# SCH_SCore-SR1_2025-01-31.net
KiCad netlist of a schematic drawn in EasyEDA
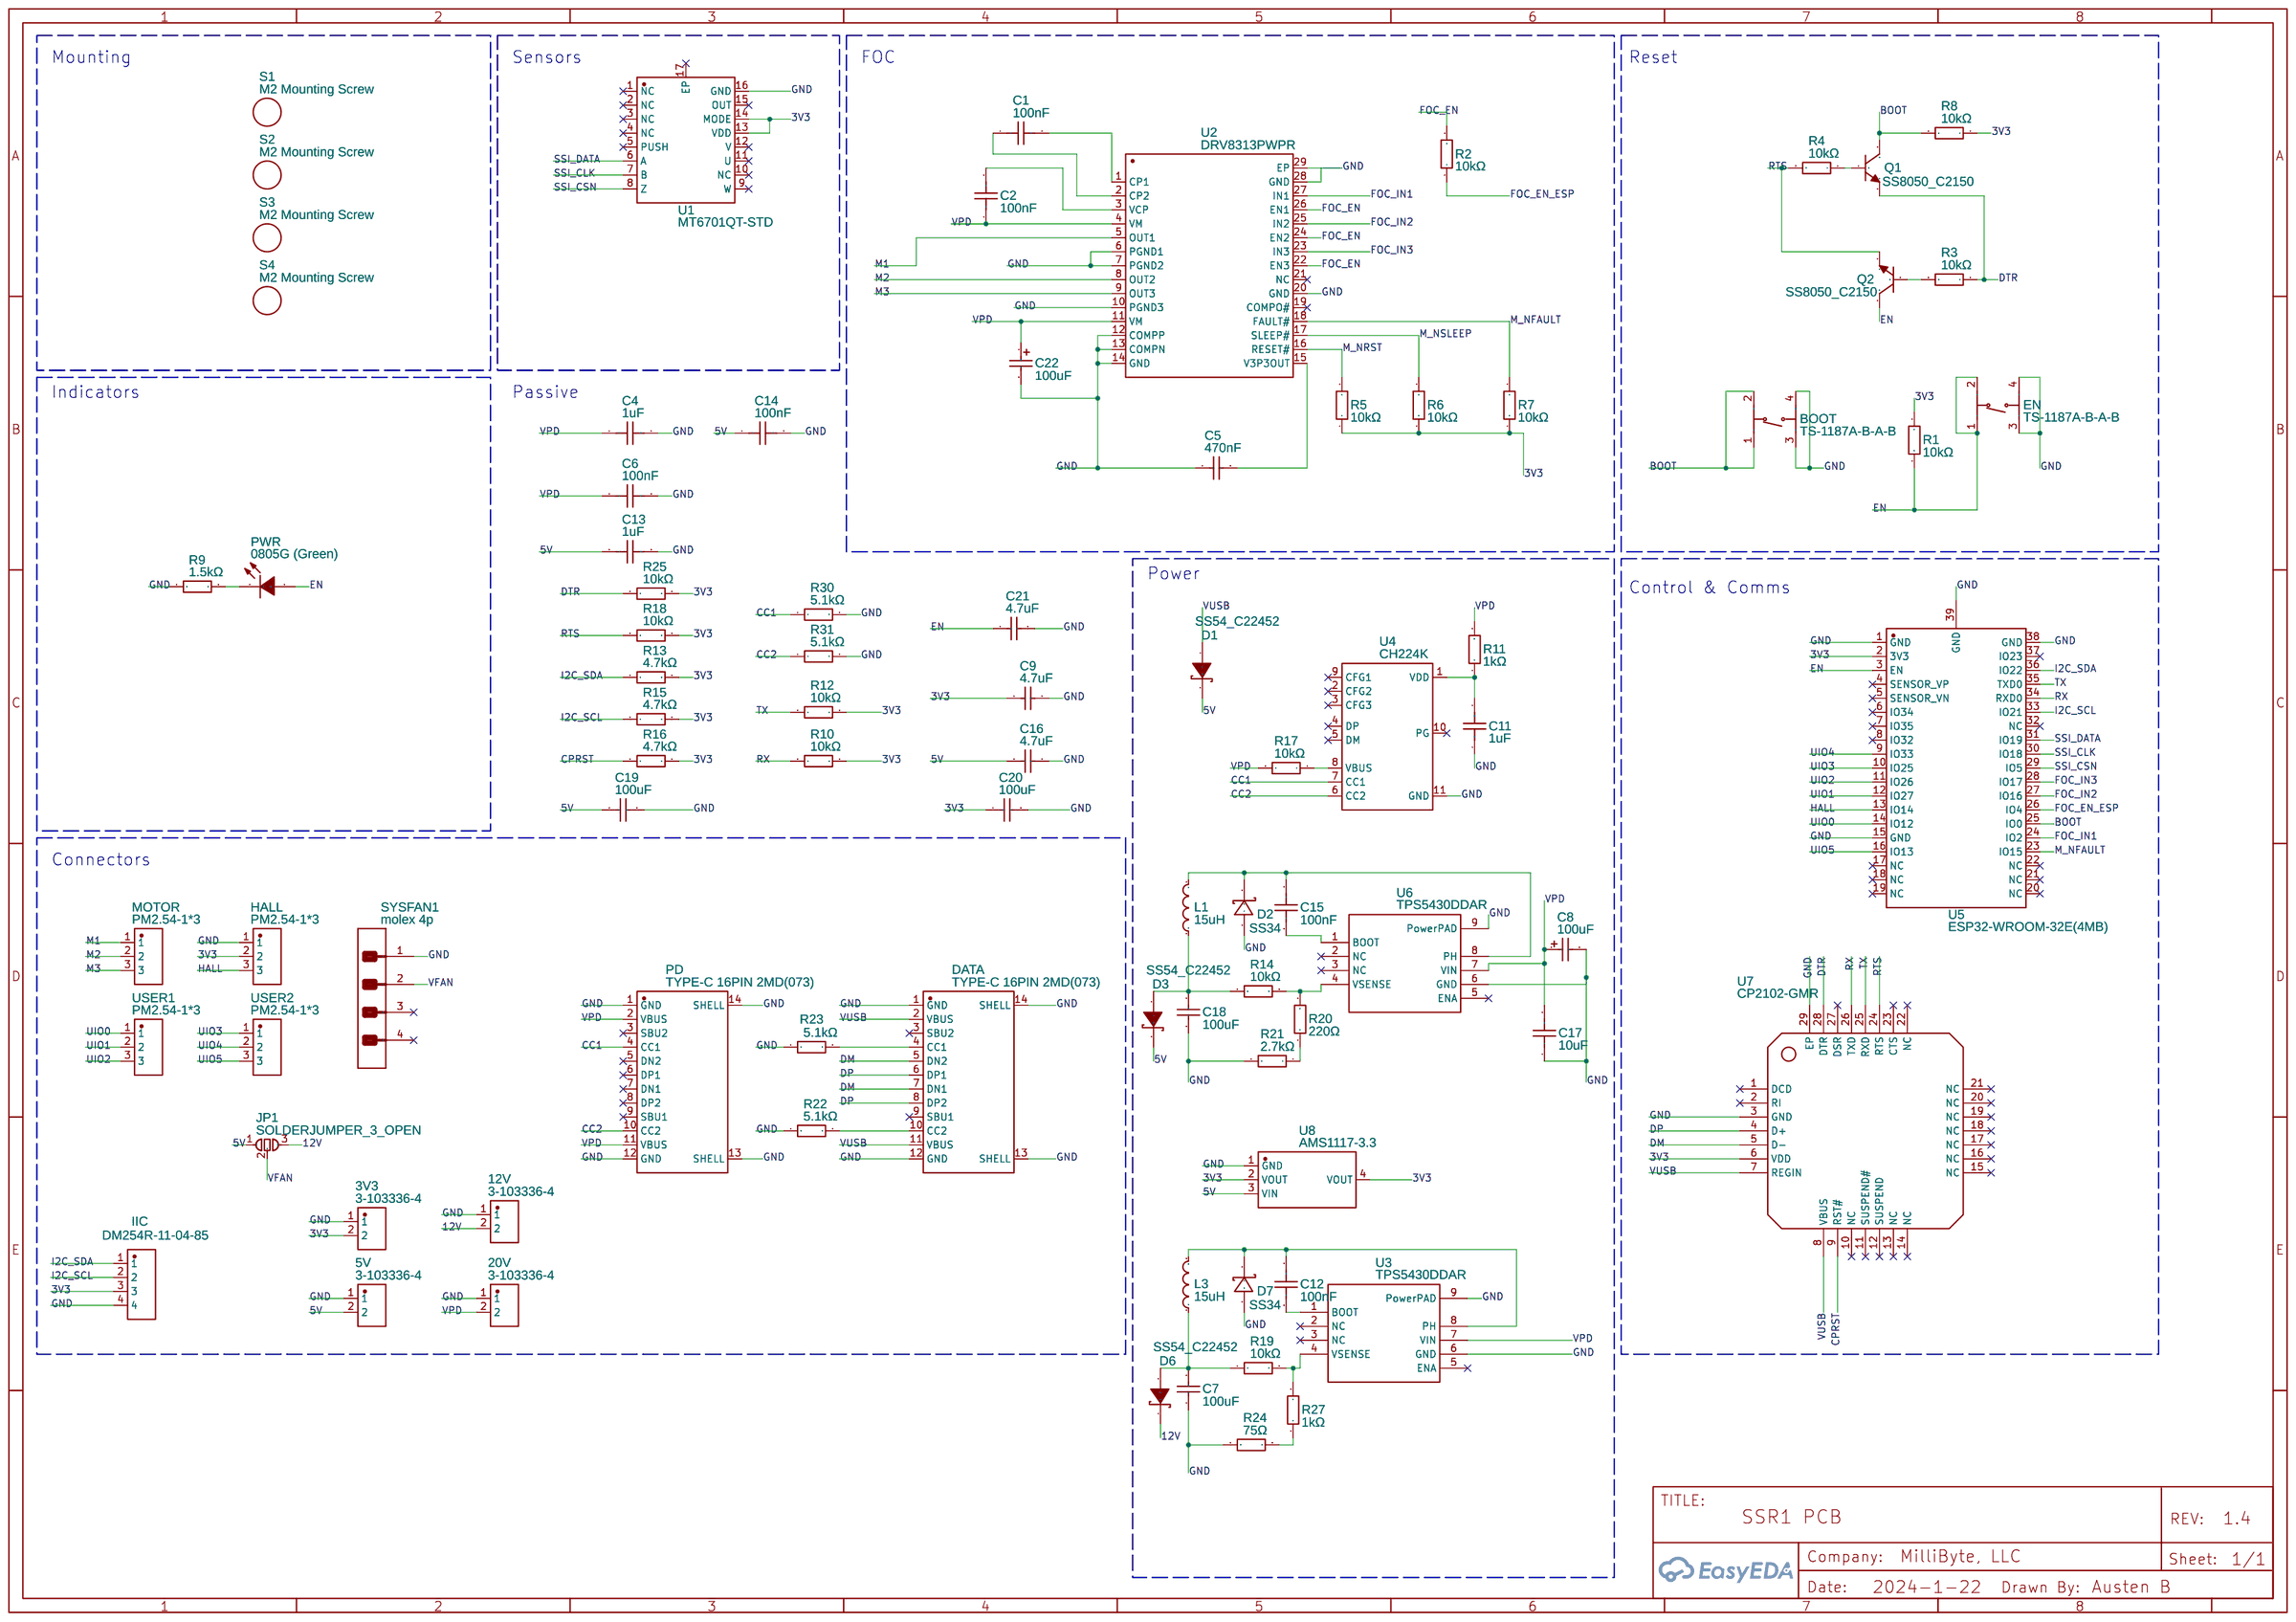
[diagram p0: schematic sheet]

(export (version "E")
  (design (tool "Eeschema 10.0.6"))
  (components
    (comp (ref "3V3")
      (value "3-103336-4")
      (fields (field (name "Manufacturer") "TE Connectivity(泰科电子)"))
      (libsource (lib "") (part "3-103336-4"))
    )
    (comp (ref "5V")
      (value "3-103336-4")
      (fields (field (name "Manufacturer") "TE Connectivity(泰科电子)"))
      (libsource (lib "") (part "3-103336-4_2"))
    )
    (comp (ref "12V")
      (value "3-103336-4")
      (fields (field (name "Manufacturer") "TE Connectivity(泰科电子)"))
      (libsource (lib "") (part "3-103336-4_1"))
    )
    (comp (ref "20V")
      (value "3-103336-4")
      (fields (field (name "Manufacturer") "TE Connectivity(泰科电子)"))
      (libsource (lib "") (part "3-103336-4_3"))
    )
    (comp (ref "BOOT")
      (value "TS-1187A-B-A-B")
      (fields (field (name "Manufacturer") "XKB Connectivity(中国星坤)"))
      (libsource (lib "") (part "TS-1187A-B-A-B_1"))
    )
    (comp (ref "C1")
      (value "100nF")
      (fields
        (field (name "Manufacturer Part") "CC0603KRX7R9BB104")
        (field (name "Manufacturer") "YAGEO(国巨)")
      )
      (libsource (lib "") (part "CC0603KRX7R9BB104"))
    )
    (comp (ref "C2")
      (value "100nF")
      (fields
        (field (name "Manufacturer Part") "CC0603KRX7R9BB104")
        (field (name "Manufacturer") "YAGEO(国巨)")
      )
      (libsource (lib "") (part "CC0603KRX7R9BB104_2"))
    )
    (comp (ref "C4")
      (value "1uF")
      (fields
        (field (name "Manufacturer Part") "CL10A105KB8NNNC")
        (field (name "Manufacturer") "SAMSUNG(三星)")
      )
      (libsource (lib "") (part "CL10A105KB8NNNC_1"))
    )
    (comp (ref "C5")
      (value "470nF")
      (fields
        (field (name "Manufacturer Part") "CL21B474KBFNNNE")
        (field (name "Manufacturer") "SAMSUNG(三星)")
      )
      (libsource (lib "") (part "CL21B474KBFNNNE"))
    )
    (comp (ref "C6")
      (value "100nF")
      (fields
        (field (name "Manufacturer Part") "CC0603KRX7R9BB104")
        (field (name "Manufacturer") "YAGEO(国巨)")
      )
      (libsource (lib "") (part "CC0603KRX7R9BB104"))
    )
    (comp (ref "C7")
      (value "100uF")
      (fields
        (field (name "Manufacturer Part") "CL31A107MQHNNNE")
        (field (name "Manufacturer") "SAMSUNG(三星)")
      )
      (libsource (lib "") (part "CL31A107MQHNNNE_1"))
    )
    (comp (ref "C8")
      (value "100uF")
      (fields (field (name "Manufacturer Part") "20TQC100MYF") (field (name "Manufacturer") "PANASONIC(松下)"))
      (libsource (lib "") (part "20TQC100MYF_1"))
    )
    (comp (ref "C9")
      (value "4.7uF")
      (fields
        (field (name "Manufacturer Part") "CL05A475MP5NRNC")
        (field (name "Manufacturer") "SAMSUNG(三星)")
      )
      (libsource (lib "") (part "CL05A475MP5NRNC"))
    )
    (comp (ref "C11")
      (value "1uF")
      (fields
        (field (name "Manufacturer Part") "CL10A105KB8NNNC")
        (field (name "Manufacturer") "SAMSUNG(三星)")
      )
      (libsource (lib "") (part "CL10A105KB8NNNC"))
    )
    (comp (ref "C12")
      (value "100nF")
      (fields
        (field (name "Manufacturer Part") "CC0603KRX7R9BB104")
        (field (name "Manufacturer") "YAGEO(国巨)")
      )
      (libsource (lib "") (part "CC0603KRX7R9BB104_1"))
    )
    (comp (ref "C13")
      (value "1uF")
      (fields
        (field (name "Manufacturer Part") "CL10A105KB8NNNC")
        (field (name "Manufacturer") "SAMSUNG(三星)")
      )
      (libsource (lib "") (part "CL10A105KB8NNNC_1"))
    )
    (comp (ref "C14")
      (value "100nF")
      (fields
        (field (name "Manufacturer Part") "CC0603KRX7R9BB104")
        (field (name "Manufacturer") "YAGEO(国巨)")
      )
      (libsource (lib "") (part "CC0603KRX7R9BB104"))
    )
    (comp (ref "C15")
      (value "100nF")
      (fields
        (field (name "Manufacturer Part") "CC0603KRX7R9BB104")
        (field (name "Manufacturer") "YAGEO(国巨)")
      )
      (libsource (lib "") (part "CC0603KRX7R9BB104_1"))
    )
    (comp (ref "C16")
      (value "4.7uF")
      (fields
        (field (name "Manufacturer Part") "CL05A475MP5NRNC")
        (field (name "Manufacturer") "SAMSUNG(三星)")
      )
      (libsource (lib "") (part "CL05A475MP5NRNC"))
    )
    (comp (ref "C17")
      (value "10uF")
      (fields
        (field (name "Manufacturer Part") "CL21A106KAYNNNE")
        (field (name "Manufacturer") "SAMSUNG(三星)")
      )
      (libsource (lib "") (part "CL21A106KAYNNNE"))
    )
    (comp (ref "C18")
      (value "100uF")
      (fields
        (field (name "Manufacturer Part") "CL31A107MQHNNNE")
        (field (name "Manufacturer") "SAMSUNG(三星)")
      )
      (libsource (lib "") (part "CL31A107MQHNNNE_1"))
    )
    (comp (ref "C19")
      (value "100uF")
      (fields
        (field (name "Manufacturer Part") "CL31A107MQHNNNE")
        (field (name "Manufacturer") "SAMSUNG(三星)")
      )
      (libsource (lib "") (part "CL31A107MQHNNNE"))
    )
    (comp (ref "C20")
      (value "100uF")
      (fields
        (field (name "Manufacturer Part") "CL31A107MQHNNNE")
        (field (name "Manufacturer") "SAMSUNG(三星)")
      )
      (libsource (lib "") (part "CL31A107MQHNNNE"))
    )
    (comp (ref "C21")
      (value "4.7uF")
      (fields
        (field (name "Manufacturer Part") "CL05A475MP5NRNC")
        (field (name "Manufacturer") "SAMSUNG(三星)")
      )
      (libsource (lib "") (part "CL05A475MP5NRNC"))
    )
    (comp (ref "C22")
      (value "100uF")
      (fields (field (name "Manufacturer Part") "20TQC100MYF") (field (name "Manufacturer") "PANASONIC(松下)"))
      (libsource (lib "") (part "20TQC100MYF"))
    )
    (comp (ref "D1")
      (value "SS54_C22452")
      (fields (field (name "Manufacturer Part") "SS54") (field (name "Manufacturer") "MDD"))
      (libsource (lib "") (part "SS54_C22452"))
    )
    (comp (ref "D2")
      (value "SS34")
      (fields (field (name "Manufacturer") "MDD(辰达半导体)"))
      (libsource (lib "") (part "SS34_C8678"))
    )
    (comp (ref "D3")
      (value "SS54_C22452")
      (fields (field (name "Manufacturer Part") "SS54") (field (name "Manufacturer") "MDD"))
      (libsource (lib "") (part "SS54_C22452"))
    )
    (comp (ref "D6")
      (value "SS54_C22452")
      (fields (field (name "Manufacturer Part") "SS54") (field (name "Manufacturer") "MDD"))
      (libsource (lib "") (part "SS54_C22452"))
    )
    (comp (ref "D7")
      (value "SS34")
      (fields (field (name "Manufacturer") "MDD(辰达半导体)"))
      (libsource (lib "") (part "SS34_C8678"))
    )
    (comp (ref "DATA")
      (value "TYPE-C 16PIN 2MD(073)")
      (fields (field (name "Manufacturer") "SHOU HAN(首韩)"))
      (libsource (lib "") (part "TYPE-C 16PIN 2MD(073)_1"))
    )
    (comp (ref "EN")
      (value "TS-1187A-B-A-B")
      (fields (field (name "Manufacturer") "XKB Connectivity(中国星坤)"))
      (libsource (lib "") (part "TS-1187A-B-A-B"))
    )
    (comp (ref "HALL")
      (value "PM2.54-1*3")
      (fields (field (name "Manufacturer") "ZHOURI(洲日)"))
      (libsource (lib "") (part "PM2.54-1*3_2"))
    )
    (comp (ref "IIC")
      (value "DM254R-11-04-85")
      (fields (field (name "Manufacturer") "DEALON(德艺隆)"))
      (libsource (lib "") (part "DM254R-11-04-85"))
    )
    (comp (ref "JP1") (value "SOLDERJUMPER_3_OPEN") (libsource (lib "") (part "SOLDERJUMPER_3_OPEN")))
    (comp (ref "L1")
      (value "15uH")
      (fields
        (field (name "Manufacturer Part") "MWSA0603S-150MT")
        (field (name "Manufacturer") "Sunlord(顺络)")
      )
      (libsource (lib "") (part "MWSA0603S-150MT_1"))
    )
    (comp (ref "L3")
      (value "15uH")
      (fields
        (field (name "Manufacturer Part") "MWSA0603S-150MT")
        (field (name "Manufacturer") "Sunlord(顺络)")
      )
      (libsource (lib "") (part "MWSA0603S-150MT"))
    )
    (comp (ref "MOTOR")
      (value "PM2.54-1*3")
      (fields (field (name "Manufacturer") "ZHOURI(洲日)"))
      (libsource (lib "") (part "PM2.54-1*3_1"))
    )
    (comp (ref "PD")
      (value "TYPE-C 16PIN 2MD(073)")
      (fields (field (name "Manufacturer") "SHOU HAN(首韩)"))
      (libsource (lib "") (part "TYPE-C 16PIN 2MD(073)"))
    )
    (comp (ref "PWR")
      (value "0805G (Green)")
      (fields (field (name "Manufacturer Part") "KT-0805G") (field (name "Manufacturer") "KENTO"))
      (libsource (lib "") (part "0805G (Green)"))
    )
    (comp (ref "Q1")
      (value "SS8050_C2150")
      (fields (field (name "Manufacturer Part") "SS8050") (field (name "Manufacturer") "CJ(江苏长电/长晶)"))
      (libsource (lib "") (part "SS8050_C2150"))
    )
    (comp (ref "Q2")
      (value "SS8050_C2150")
      (fields (field (name "Manufacturer Part") "SS8050") (field (name "Manufacturer") "CJ(江苏长电/长晶)"))
      (libsource (lib "") (part "SS8050_C2150_1"))
    )
    (comp (ref "R1")
      (value "10kΩ")
      (fields
        (field (name "Manufacturer Part") "0402WGF1002TCE")
        (field (name "Manufacturer") "UNI-ROYAL(厚声)")
      )
      (libsource (lib "") (part "0402WGF1002TCE_2"))
    )
    (comp (ref "R2")
      (value "10kΩ")
      (fields
        (field (name "Manufacturer Part") "0603WAF1002T5E")
        (field (name "Manufacturer") "UNI-ROYAL(厚声)")
      )
      (libsource (lib "") (part "0603WAF1002T5E"))
    )
    (comp (ref "R3")
      (value "10kΩ")
      (fields
        (field (name "Manufacturer Part") "0402WGF1002TCE")
        (field (name "Manufacturer") "UNI-ROYAL(厚声)")
      )
      (libsource (lib "") (part "0402WGF1002TCE"))
    )
    (comp (ref "R4")
      (value "10kΩ")
      (fields
        (field (name "Manufacturer Part") "0402WGF1002TCE")
        (field (name "Manufacturer") "UNI-ROYAL(厚声)")
      )
      (libsource (lib "") (part "0402WGF1002TCE"))
    )
    (comp (ref "R5")
      (value "10kΩ")
      (fields
        (field (name "Manufacturer Part") "0402WGF1002TCE")
        (field (name "Manufacturer") "UNI-ROYAL(厚声)")
      )
      (libsource (lib "") (part "0402WGF1002TCE_2"))
    )
    (comp (ref "R6")
      (value "10kΩ")
      (fields
        (field (name "Manufacturer Part") "0402WGF1002TCE")
        (field (name "Manufacturer") "UNI-ROYAL(厚声)")
      )
      (libsource (lib "") (part "0402WGF1002TCE_2"))
    )
    (comp (ref "R7")
      (value "10kΩ")
      (fields
        (field (name "Manufacturer Part") "0402WGF1002TCE")
        (field (name "Manufacturer") "UNI-ROYAL(厚声)")
      )
      (libsource (lib "") (part "0402WGF1002TCE_2"))
    )
    (comp (ref "R8")
      (value "10kΩ")
      (fields
        (field (name "Manufacturer Part") "0402WGF1002TCE")
        (field (name "Manufacturer") "UNI-ROYAL(厚声)")
      )
      (libsource (lib "") (part "0402WGF1002TCE"))
    )
    (comp (ref "R9")
      (value "1.5kΩ")
      (fields
        (field (name "Manufacturer Part") "0603WAF1501T5E")
        (field (name "Manufacturer") "UNI-ROYAL(厚声)")
      )
      (libsource (lib "") (part "0603WAF1501T5E"))
    )
    (comp (ref "R10")
      (value "10kΩ")
      (fields
        (field (name "Manufacturer Part") "0402WGF1002TCE")
        (field (name "Manufacturer") "UNI-ROYAL(厚声)")
      )
      (libsource (lib "") (part "0402WGF1002TCE_1"))
    )
    (comp (ref "R11")
      (value "1kΩ")
      (fields
        (field (name "Manufacturer Part") "0402WGF1001TCE")
        (field (name "Manufacturer") "UNI-ROYAL(厚声)")
      )
      (libsource (lib "") (part "0402WGF1001TCE"))
    )
    (comp (ref "R12")
      (value "10kΩ")
      (fields
        (field (name "Manufacturer Part") "0402WGF1002TCE")
        (field (name "Manufacturer") "UNI-ROYAL(厚声)")
      )
      (libsource (lib "") (part "0402WGF1002TCE_1"))
    )
    (comp (ref "R13")
      (value "4.7kΩ")
      (fields
        (field (name "Manufacturer Part") "0402WGF4701TCE")
        (field (name "Manufacturer") "UNI-ROYAL(厚声)")
      )
      (libsource (lib "") (part "0402WGF4701TCE"))
    )
    (comp (ref "R14")
      (value "10kΩ")
      (fields
        (field (name "Manufacturer Part") "0402WGF1002TCE")
        (field (name "Manufacturer") "UNI-ROYAL(厚声)")
      )
      (libsource (lib "") (part "0402WGF1002TCE_1"))
    )
    (comp (ref "R15")
      (value "4.7kΩ")
      (fields
        (field (name "Manufacturer Part") "0402WGF4701TCE")
        (field (name "Manufacturer") "UNI-ROYAL(厚声)")
      )
      (libsource (lib "") (part "0402WGF4701TCE"))
    )
    (comp (ref "R16")
      (value "4.7kΩ")
      (fields
        (field (name "Manufacturer Part") "0402WGF4701TCE")
        (field (name "Manufacturer") "UNI-ROYAL(厚声)")
      )
      (libsource (lib "") (part "0402WGF4701TCE"))
    )
    (comp (ref "R17")
      (value "10kΩ")
      (fields
        (field (name "Manufacturer Part") "0402WGF1002TCE")
        (field (name "Manufacturer") "UNI-ROYAL(厚声)")
      )
      (libsource (lib "") (part "0402WGF1002TCE"))
    )
    (comp (ref "R18")
      (value "10kΩ")
      (fields
        (field (name "Manufacturer Part") "0402WGF1002TCE")
        (field (name "Manufacturer") "UNI-ROYAL(厚声)")
      )
      (libsource (lib "") (part "0402WGF1002TCE_1"))
    )
    (comp (ref "R19")
      (value "10kΩ")
      (fields
        (field (name "Manufacturer Part") "0402WGF1002TCE")
        (field (name "Manufacturer") "UNI-ROYAL(厚声)")
      )
      (libsource (lib "") (part "0402WGF1002TCE_1"))
    )
    (comp (ref "R20")
      (value "220Ω")
      (fields
        (field (name "Manufacturer Part") "0603WAF2200T5E")
        (field (name "Manufacturer") "UNI-ROYAL(厚声)")
      )
      (libsource (lib "") (part "0603WAF2200T5E"))
    )
    (comp (ref "R21")
      (value "2.7kΩ")
      (fields (field (name "Manufacturer Part") "0603WAF2701T5E") (field (name "Manufacturer") "UniOhm"))
      (libsource (lib "") (part "0603WAF2701T5E"))
    )
    (comp (ref "R22")
      (value "5.1kΩ")
      (fields
        (field (name "Manufacturer Part") "0402WGF5101TCE")
        (field (name "Manufacturer") "UNI-ROYAL(厚声)")
      )
      (libsource (lib "") (part "0402WGF5101TCE"))
    )
    (comp (ref "R23")
      (value "5.1kΩ")
      (fields
        (field (name "Manufacturer Part") "0402WGF5101TCE")
        (field (name "Manufacturer") "UNI-ROYAL(厚声)")
      )
      (libsource (lib "") (part "0402WGF5101TCE"))
    )
    (comp (ref "R24")
      (value "75Ω")
      (fields
        (field (name "Manufacturer Part") "0603WAF750JT5E")
        (field (name "Manufacturer") "UNI-ROYAL(厚声)")
      )
      (libsource (lib "") (part "0603WAF750JT5E"))
    )
    (comp (ref "R25")
      (value "10kΩ")
      (fields
        (field (name "Manufacturer Part") "0402WGF1002TCE")
        (field (name "Manufacturer") "UNI-ROYAL(厚声)")
      )
      (libsource (lib "") (part "0402WGF1002TCE_1"))
    )
    (comp (ref "R27")
      (value "1kΩ")
      (fields
        (field (name "Manufacturer Part") "0603WAF1001T5E")
        (field (name "Manufacturer") "UNI-ROYAL(厚声)")
      )
      (libsource (lib "") (part "0603WAF1001T5E"))
    )
    (comp (ref "R30")
      (value "5.1kΩ")
      (fields
        (field (name "Manufacturer Part") "0402WGF5101TCE")
        (field (name "Manufacturer") "UNI-ROYAL(厚声)")
      )
      (libsource (lib "") (part "0402WGF5101TCE"))
    )
    (comp (ref "R31")
      (value "5.1kΩ")
      (fields
        (field (name "Manufacturer Part") "0402WGF5101TCE")
        (field (name "Manufacturer") "UNI-ROYAL(厚声)")
      )
      (libsource (lib "") (part "0402WGF5101TCE"))
    )
    (comp (ref "S1") (value "M2 Mounting Screw") (libsource (lib "") (part "M2 Mounting Screw")))
    (comp (ref "S2") (value "M2 Mounting Screw") (libsource (lib "") (part "M2 Mounting Screw")))
    (comp (ref "S3") (value "M2 Mounting Screw") (libsource (lib "") (part "M2 Mounting Screw")))
    (comp (ref "S4") (value "M2 Mounting Screw") (libsource (lib "") (part "M2 Mounting Screw")))
    (comp (ref "SYSFAN1") (value "molex 4p") (libsource (lib "") (part "molex 4p")))
    (comp (ref "U1")
      (value "MT6701QT-STD")
      (fields (field (name "Manufacturer") "MagnTek(麦歌恩)"))
      (libsource (lib "") (part "MT6701QT-STD"))
    )
    (comp (ref "U2")
      (value "DRV8313PWPR")
      (fields (field (name "Manufacturer") "Texas Instruments"))
      (libsource (lib "") (part "DRV8313PWPR"))
    )
    (comp (ref "U3")
      (value "TPS5430DDAR")
      (fields (field (name "Manufacturer") "TI(德州仪器)"))
      (libsource (lib "") (part "TPS5430DDAR"))
    )
    (comp (ref "U4")
      (value "CH224K")
      (fields (field (name "Manufacturer") "WCH(南京沁恒)"))
      (libsource (lib "") (part "CH224K"))
    )
    (comp (ref "U5")
      (value "ESP32-WROOM-32E(4MB)")
      (fields
        (field (name "Manufacturer Part") "ESP32-WROOM-32E-N4")
        (field (name "Manufacturer") "ESPRESSIF(乐鑫)")
      )
      (libsource (lib "") (part "ESP32-WROOM-32E(4MB)"))
    )
    (comp (ref "U6")
      (value "TPS5430DDAR")
      (fields (field (name "Manufacturer") "TI(德州仪器)"))
      (libsource (lib "") (part "TPS5430DDAR"))
    )
    (comp (ref "U7")
      (value "CP2102-GMR")
      (fields (field (name "Manufacturer") "SKYWORKS/SILICON LABS(芯科)"))
      (libsource (lib "") (part "CP2102-GMR"))
    )
    (comp (ref "U8")
      (value "AMS1117-3.3")
      (fields (field (name "Manufacturer") "AMS"))
      (libsource (lib "") (part "AMS1117-3.3"))
    )
    (comp (ref "USER1")
      (value "PM2.54-1*3")
      (fields (field (name "Manufacturer") "ZHOURI(洲日)"))
      (libsource (lib "") (part "PM2.54-1*3"))
    )
    (comp (ref "USER2")
      (value "PM2.54-1*3")
      (fields (field (name "Manufacturer") "ZHOURI(洲日)"))
      (libsource (lib "") (part "PM2.54-1*3"))
    )
  )
  (nets
    (net (code "1") (name "/3V3") (class "Default")
      (node (ref "3V3") (pin "2") (pinfunction "2_2") (pintype "unspecified"))
      (node (ref "C20") (pin "1") (pinfunction "1_1") (pintype "input"))
      (node (ref "C9") (pin "1") (pinfunction "1_1") (pintype "input"))
      (node (ref "HALL") (pin "2") (pinfunction "2_2") (pintype "unspecified"))
      (node (ref "IIC") (pin "3") (pinfunction "3_3") (pintype "unspecified"))
      (node (ref "R1") (pin "2") (pinfunction "2_2") (pintype "input"))
      (node (ref "R10") (pin "2") (pinfunction "2_2") (pintype "input"))
      (node (ref "R12") (pin "2") (pinfunction "2_2") (pintype "input"))
      (node (ref "R13") (pin "2") (pinfunction "2_2") (pintype "input"))
      (node (ref "R15") (pin "2") (pinfunction "2_2") (pintype "input"))
      (node (ref "R16") (pin "2") (pinfunction "2_2") (pintype "input"))
      (node (ref "R18") (pin "2") (pinfunction "2_2") (pintype "input"))
      (node (ref "R25") (pin "2") (pinfunction "2_2") (pintype "input"))
      (node (ref "R5") (pin "1") (pinfunction "1_1") (pintype "input"))
      (node (ref "R6") (pin "1") (pinfunction "1_1") (pintype "input"))
      (node (ref "R7") (pin "1") (pinfunction "1_1") (pintype "input"))
      (node (ref "R8") (pin "1") (pinfunction "1_1") (pintype "input"))
      (node (ref "U1") (pin "13") (pinfunction "VDD_13") (pintype "unspecified"))
      (node (ref "U1") (pin "14") (pinfunction "MODE_14") (pintype "unspecified"))
      (node (ref "U5") (pin "2") (pinfunction "3V3_2") (pintype "unspecified"))
      (node (ref "U7") (pin "6") (pinfunction "VDD_6") (pintype "unspecified"))
      (node (ref "U8") (pin "2") (pinfunction "VOUT_2") (pintype "unspecified"))
      (node (ref "U8") (pin "4") (pinfunction "VOUT_4") (pintype "unspecified"))
    )
    (net (code "2") (name "/5V") (class "Default")
      (node (ref "5V") (pin "2") (pinfunction "2_2") (pintype "unspecified"))
      (node (ref "C13") (pin "1") (pinfunction "1_1") (pintype "unspecified"))
      (node (ref "C14") (pin "1") (pinfunction "1_1") (pintype "unspecified"))
      (node (ref "C16") (pin "1") (pinfunction "1_1") (pintype "input"))
      (node (ref "C19") (pin "1") (pinfunction "1_1") (pintype "input"))
      (node (ref "D1") (pin "2") (pinfunction "K_2") (pintype "unspecified"))
      (node (ref "D3") (pin "2") (pinfunction "K_2") (pintype "unspecified"))
      (node (ref "JP1") (pin "1") (pinfunction "A_1") (pintype "unspecified"))
      (node (ref "U8") (pin "3") (pinfunction "VIN_3") (pintype "unspecified"))
    )
    (net (code "3") (name "/12V") (class "Default")
      (node (ref "12V") (pin "2") (pinfunction "2_2") (pintype "unspecified"))
      (node (ref "D6") (pin "2") (pinfunction "K_2") (pintype "unspecified"))
      (node (ref "JP1") (pin "3") (pinfunction "B_3") (pintype "unspecified"))
    )
    (net (code "4") (name "/BOOT") (class "Default")
      (node (ref "BOOT") (pin "1") (pinfunction "A_1") (pintype "unspecified"))
      (node (ref "BOOT") (pin "2") (pinfunction "B_2") (pintype "unspecified"))
      (node (ref "Q1") (pin "3") (pinfunction "C_3") (pintype "unspecified"))
      (node (ref "R8") (pin "2") (pinfunction "2_2") (pintype "input"))
      (node (ref "U5") (pin "25") (pinfunction "IO0_25") (pintype "unspecified"))
    )
    (net (code "5") (name "/CC1") (class "Default")
      (node (ref "PD") (pin "4") (pinfunction "CC1_4") (pintype "unspecified"))
      (node (ref "R30") (pin "1") (pinfunction "1_1") (pintype "input"))
      (node (ref "U4") (pin "7") (pinfunction "CC1_7") (pintype "unspecified"))
    )
    (net (code "6") (name "/CC2") (class "Default")
      (node (ref "PD") (pin "10") (pinfunction "CC2_10") (pintype "unspecified"))
      (node (ref "R31") (pin "1") (pinfunction "1_1") (pintype "input"))
      (node (ref "U4") (pin "6") (pinfunction "CC2_6") (pintype "unspecified"))
    )
    (net (code "7") (name "/CPRST") (class "Default")
      (node (ref "R16") (pin "1") (pinfunction "1_1") (pintype "input"))
      (node (ref "U7") (pin "9") (pinfunction "RST#_9") (pintype "unspecified"))
    )
    (net (code "8") (name "/DM") (class "Default")
      (node (ref "DATA") (pin "5") (pinfunction "DN2_5") (pintype "unspecified"))
      (node (ref "DATA") (pin "7") (pinfunction "DN1_7") (pintype "unspecified"))
      (node (ref "U7") (pin "5") (pinfunction "D-_5") (pintype "unspecified"))
    )
    (net (code "9") (name "/DP") (class "Default")
      (node (ref "DATA") (pin "6") (pinfunction "DP1_6") (pintype "unspecified"))
      (node (ref "DATA") (pin "8") (pinfunction "DP2_8") (pintype "unspecified"))
      (node (ref "U7") (pin "4") (pinfunction "D+_4") (pintype "unspecified"))
    )
    (net (code "10") (name "/DTR") (class "Default")
      (node (ref "Q1") (pin "2") (pinfunction "E_2") (pintype "unspecified"))
      (node (ref "R25") (pin "1") (pinfunction "1_1") (pintype "input"))
      (node (ref "R3") (pin "1") (pinfunction "1_1") (pintype "input"))
      (node (ref "U7") (pin "28") (pinfunction "DTR_28") (pintype "unspecified"))
    )
    (net (code "11") (name "/EN") (class "Default")
      (node (ref "C21") (pin "1") (pinfunction "1_1") (pintype "input"))
      (node (ref "EN") (pin "1") (pinfunction "A_1") (pintype "unspecified"))
      (node (ref "EN") (pin "2") (pinfunction "B_2") (pintype "unspecified"))
      (node (ref "PWR") (pin "1") (pinfunction "A_1") (pintype "unspecified"))
      (node (ref "Q2") (pin "3") (pinfunction "C_3") (pintype "unspecified"))
      (node (ref "R1") (pin "1") (pinfunction "1_1") (pintype "input"))
      (node (ref "U5") (pin "3") (pinfunction "EN_3") (pintype "unspecified"))
    )
    (net (code "12") (name "/FOC_EN") (class "Default")
      (node (ref "R2") (pin "2") (pinfunction "2_2") (pintype "input"))
      (node (ref "U2") (pin "22") (pinfunction "EN3_22") (pintype "unspecified"))
      (node (ref "U2") (pin "24") (pinfunction "EN2_24") (pintype "unspecified"))
      (node (ref "U2") (pin "26") (pinfunction "EN1_26") (pintype "unspecified"))
    )
    (net (code "13") (name "/FOC_EN_ESP") (class "Default")
      (node (ref "R2") (pin "1") (pinfunction "1_1") (pintype "input"))
      (node (ref "U5") (pin "26") (pinfunction "IO4_26") (pintype "unspecified"))
    )
    (net (code "14") (name "/FOC_IN1") (class "Default")
      (node (ref "U2") (pin "27") (pinfunction "IN1_27") (pintype "unspecified"))
      (node (ref "U5") (pin "24") (pinfunction "IO2_24") (pintype "unspecified"))
    )
    (net (code "15") (name "/FOC_IN2") (class "Default")
      (node (ref "U2") (pin "25") (pinfunction "IN2_25") (pintype "unspecified"))
      (node (ref "U5") (pin "27") (pinfunction "IO16_27") (pintype "unspecified"))
    )
    (net (code "16") (name "/FOC_IN3") (class "Default")
      (node (ref "U2") (pin "23") (pinfunction "IN3_23") (pintype "unspecified"))
      (node (ref "U5") (pin "28") (pinfunction "IO17_28") (pintype "unspecified"))
    )
    (net (code "17") (name "/GND") (class "Default")
      (node (ref "12V") (pin "1") (pinfunction "1_1") (pintype "unspecified"))
      (node (ref "20V") (pin "1") (pinfunction "1_1") (pintype "unspecified"))
      (node (ref "3V3") (pin "1") (pinfunction "1_1") (pintype "unspecified"))
      (node (ref "5V") (pin "1") (pinfunction "1_1") (pintype "unspecified"))
      (node (ref "BOOT") (pin "3") (pinfunction "C_3") (pintype "unspecified"))
      (node (ref "BOOT") (pin "4") (pinfunction "D_4") (pintype "unspecified"))
      (node (ref "C11") (pin "1") (pinfunction "1_1") (pintype "unspecified"))
      (node (ref "C13") (pin "2") (pinfunction "2_2") (pintype "unspecified"))
      (node (ref "C14") (pin "2") (pinfunction "2_2") (pintype "unspecified"))
      (node (ref "C16") (pin "2") (pinfunction "2_2") (pintype "input"))
      (node (ref "C17") (pin "1") (pinfunction "1_1") (pintype "unspecified"))
      (node (ref "C18") (pin "1") (pinfunction "1_1") (pintype "input"))
      (node (ref "C19") (pin "2") (pinfunction "2_2") (pintype "input"))
      (node (ref "C20") (pin "2") (pinfunction "2_2") (pintype "input"))
      (node (ref "C21") (pin "2") (pinfunction "2_2") (pintype "input"))
      (node (ref "C22") (pin "2") (pinfunction "2_2") (pintype "input"))
      (node (ref "C4") (pin "2") (pinfunction "2_2") (pintype "unspecified"))
      (node (ref "C5") (pin "1") (pinfunction "1_1") (pintype "unspecified"))
      (node (ref "C6") (pin "2") (pinfunction "2_2") (pintype "unspecified"))
      (node (ref "C7") (pin "1") (pinfunction "1_1") (pintype "input"))
      (node (ref "C8") (pin "2") (pinfunction "2_2") (pintype "input"))
      (node (ref "C9") (pin "2") (pinfunction "2_2") (pintype "input"))
      (node (ref "D2") (pin "2") (pinfunction "A_2") (pintype "unspecified"))
      (node (ref "D7") (pin "2") (pinfunction "A_2") (pintype "unspecified"))
      (node (ref "DATA") (pin "1") (pinfunction "GND_1") (pintype "unspecified"))
      (node (ref "DATA") (pin "12") (pinfunction "GND_12") (pintype "unspecified"))
      (node (ref "DATA") (pin "13") (pinfunction "SHELL_13") (pintype "unspecified"))
      (node (ref "DATA") (pin "14") (pinfunction "SHELL_14") (pintype "unspecified"))
      (node (ref "EN") (pin "3") (pinfunction "C_3") (pintype "unspecified"))
      (node (ref "EN") (pin "4") (pinfunction "D_4") (pintype "unspecified"))
      (node (ref "HALL") (pin "1") (pinfunction "1_1") (pintype "unspecified"))
      (node (ref "IIC") (pin "4") (pinfunction "4_4") (pintype "unspecified"))
      (node (ref "PD") (pin "1") (pinfunction "GND_1") (pintype "unspecified"))
      (node (ref "PD") (pin "12") (pinfunction "GND_12") (pintype "unspecified"))
      (node (ref "PD") (pin "13") (pinfunction "SHELL_13") (pintype "unspecified"))
      (node (ref "PD") (pin "14") (pinfunction "SHELL_14") (pintype "unspecified"))
      (node (ref "R21") (pin "2") (pinfunction "2_2") (pintype "unspecified"))
      (node (ref "R22") (pin "1") (pinfunction "1_1") (pintype "input"))
      (node (ref "R23") (pin "1") (pinfunction "1_1") (pintype "input"))
      (node (ref "R24") (pin "1") (pinfunction "1_1") (pintype "input"))
      (node (ref "R30") (pin "2") (pinfunction "2_2") (pintype "input"))
      (node (ref "R31") (pin "2") (pinfunction "2_2") (pintype "input"))
      (node (ref "R9") (pin "1") (pinfunction "1_1") (pintype "input"))
      (node (ref "SYSFAN1") (pin "1") (pinfunction "1_1") (pintype "bidirectional"))
      (node (ref "U1") (pin "16") (pinfunction "GND_16") (pintype "unspecified"))
      (node (ref "U2") (pin "10") (pinfunction "PGND3_10") (pintype "unspecified"))
      (node (ref "U2") (pin "12") (pinfunction "COMPP_12") (pintype "unspecified"))
      (node (ref "U2") (pin "13") (pinfunction "COMPN_13") (pintype "unspecified"))
      (node (ref "U2") (pin "14") (pinfunction "GND_14") (pintype "unspecified"))
      (node (ref "U2") (pin "20") (pinfunction "GND_20") (pintype "unspecified"))
      (node (ref "U2") (pin "28") (pinfunction "GND_28") (pintype "unspecified"))
      (node (ref "U2") (pin "29") (pinfunction "EP_29") (pintype "unspecified"))
      (node (ref "U2") (pin "6") (pinfunction "PGND1_6") (pintype "unspecified"))
      (node (ref "U2") (pin "7") (pinfunction "PGND2_7") (pintype "unspecified"))
      (node (ref "U3") (pin "6") (pinfunction "GND_6") (pintype "unspecified"))
      (node (ref "U3") (pin "9") (pinfunction "PowerPAD_9") (pintype "unspecified"))
      (node (ref "U4") (pin "11") (pinfunction "GND_11") (pintype "unspecified"))
      (node (ref "U5") (pin "1") (pinfunction "GND_1") (pintype "unspecified"))
      (node (ref "U5") (pin "15") (pinfunction "GND_15") (pintype "unspecified"))
      (node (ref "U5") (pin "38") (pinfunction "GND_38") (pintype "unspecified"))
      (node (ref "U5") (pin "39") (pinfunction "GND_39") (pintype "unspecified"))
      (node (ref "U6") (pin "6") (pinfunction "GND_6") (pintype "unspecified"))
      (node (ref "U6") (pin "9") (pinfunction "PowerPAD_9") (pintype "unspecified"))
      (node (ref "U7") (pin "29") (pinfunction "EP_29") (pintype "unspecified"))
      (node (ref "U7") (pin "3") (pinfunction "GND_3") (pintype "unspecified"))
      (node (ref "U8") (pin "1") (pinfunction "GND_1") (pintype "unspecified"))
    )
    (net (code "18") (name "/HALL") (class "Default")
      (node (ref "HALL") (pin "3") (pinfunction "3_3") (pintype "unspecified"))
      (node (ref "U5") (pin "13") (pinfunction "IO14_13") (pintype "unspecified"))
    )
    (net (code "19") (name "/I2C_SCL") (class "Default")
      (node (ref "IIC") (pin "2") (pinfunction "2_2") (pintype "unspecified"))
      (node (ref "R15") (pin "1") (pinfunction "1_1") (pintype "input"))
      (node (ref "U5") (pin "33") (pinfunction "IO21_33") (pintype "unspecified"))
    )
    (net (code "20") (name "/I2C_SDA") (class "Default")
      (node (ref "IIC") (pin "1") (pinfunction "1_1") (pintype "unspecified"))
      (node (ref "R13") (pin "1") (pinfunction "1_1") (pintype "input"))
      (node (ref "U5") (pin "36") (pinfunction "IO22_36") (pintype "unspecified"))
    )
    (net (code "21") (name "/M1") (class "Default")
      (node (ref "MOTOR") (pin "1") (pinfunction "1_1") (pintype "unspecified"))
      (node (ref "U2") (pin "5") (pinfunction "OUT1_5") (pintype "unspecified"))
    )
    (net (code "22") (name "/M2") (class "Default")
      (node (ref "MOTOR") (pin "2") (pinfunction "2_2") (pintype "unspecified"))
      (node (ref "U2") (pin "8") (pinfunction "OUT2_8") (pintype "unspecified"))
    )
    (net (code "23") (name "/M3") (class "Default")
      (node (ref "MOTOR") (pin "3") (pinfunction "3_3") (pintype "unspecified"))
      (node (ref "U2") (pin "9") (pinfunction "OUT3_9") (pintype "unspecified"))
    )
    (net (code "24") (name "/M_NFAULT") (class "Default")
      (node (ref "R7") (pin "2") (pinfunction "2_2") (pintype "input"))
      (node (ref "U2") (pin "18") (pinfunction "FAULT#_18") (pintype "unspecified"))
      (node (ref "U5") (pin "23") (pinfunction "IO15_23") (pintype "unspecified"))
    )
    (net (code "25") (name "/M_NRST") (class "Default")
      (node (ref "R5") (pin "2") (pinfunction "2_2") (pintype "input"))
      (node (ref "U2") (pin "16") (pinfunction "RESET#_16") (pintype "unspecified"))
    )
    (net (code "26") (name "/M_NSLEEP") (class "Default")
      (node (ref "R6") (pin "2") (pinfunction "2_2") (pintype "input"))
      (node (ref "U2") (pin "17") (pinfunction "SLEEP#_17") (pintype "unspecified"))
    )
    (net (code "27") (name "/RTS") (class "Default")
      (node (ref "Q2") (pin "2") (pinfunction "E_2") (pintype "unspecified"))
      (node (ref "R18") (pin "1") (pinfunction "1_1") (pintype "input"))
      (node (ref "R4") (pin "2") (pinfunction "2_2") (pintype "input"))
      (node (ref "U7") (pin "24") (pinfunction "RTS_24") (pintype "unspecified"))
    )
    (net (code "28") (name "/RX") (class "Default")
      (node (ref "R10") (pin "1") (pinfunction "1_1") (pintype "input"))
      (node (ref "U5") (pin "34") (pinfunction "RXD0_34") (pintype "unspecified"))
      (node (ref "U7") (pin "26") (pinfunction "TXD_26") (pintype "unspecified"))
    )
    (net (code "29") (name "/SSI_CLK") (class "Default")
      (node (ref "U1") (pin "7") (pinfunction "B_7") (pintype "unspecified"))
      (node (ref "U5") (pin "30") (pinfunction "IO18_30") (pintype "unspecified"))
    )
    (net (code "30") (name "/SSI_CSN") (class "Default")
      (node (ref "U1") (pin "8") (pinfunction "Z_8") (pintype "unspecified"))
      (node (ref "U5") (pin "29") (pinfunction "IO5_29") (pintype "unspecified"))
    )
    (net (code "31") (name "/SSI_DATA") (class "Default")
      (node (ref "U1") (pin "6") (pinfunction "A_6") (pintype "unspecified"))
      (node (ref "U5") (pin "31") (pinfunction "IO19_31") (pintype "unspecified"))
    )
    (net (code "32") (name "/TX") (class "Default")
      (node (ref "R12") (pin "1") (pinfunction "1_1") (pintype "input"))
      (node (ref "U5") (pin "35") (pinfunction "TXD0_35") (pintype "unspecified"))
      (node (ref "U7") (pin "25") (pinfunction "RXD_25") (pintype "unspecified"))
    )
    (net (code "33") (name "/UIO0") (class "Default")
      (node (ref "U5") (pin "14") (pinfunction "IO12_14") (pintype "unspecified"))
      (node (ref "USER1") (pin "1") (pinfunction "1_1") (pintype "unspecified"))
    )
    (net (code "34") (name "/UIO1") (class "Default")
      (node (ref "U5") (pin "12") (pinfunction "IO27_12") (pintype "unspecified"))
      (node (ref "USER1") (pin "2") (pinfunction "2_2") (pintype "unspecified"))
    )
    (net (code "35") (name "/UIO2") (class "Default")
      (node (ref "U5") (pin "11") (pinfunction "IO26_11") (pintype "unspecified"))
      (node (ref "USER1") (pin "3") (pinfunction "3_3") (pintype "unspecified"))
    )
    (net (code "36") (name "/UIO3") (class "Default")
      (node (ref "U5") (pin "10") (pinfunction "IO25_10") (pintype "unspecified"))
      (node (ref "USER2") (pin "1") (pinfunction "1_1") (pintype "unspecified"))
    )
    (net (code "37") (name "/UIO4") (class "Default")
      (node (ref "U5") (pin "9") (pinfunction "IO33_9") (pintype "unspecified"))
      (node (ref "USER2") (pin "2") (pinfunction "2_2") (pintype "unspecified"))
    )
    (net (code "38") (name "/UIO5") (class "Default")
      (node (ref "U5") (pin "16") (pinfunction "IO13_16") (pintype "unspecified"))
      (node (ref "USER2") (pin "3") (pinfunction "3_3") (pintype "unspecified"))
    )
    (net (code "39") (name "/VFAN") (class "Default")
      (node (ref "JP1") (pin "2") (pinfunction "C_2") (pintype "unspecified"))
      (node (ref "SYSFAN1") (pin "2") (pinfunction "2_2") (pintype "bidirectional"))
    )
    (net (code "40") (name "/VPD") (class "Default")
      (node (ref "20V") (pin "2") (pinfunction "2_2") (pintype "unspecified"))
      (node (ref "C17") (pin "2") (pinfunction "2_2") (pintype "unspecified"))
      (node (ref "C2") (pin "1") (pinfunction "1_1") (pintype "unspecified"))
      (node (ref "C22") (pin "1") (pinfunction "1_1") (pintype "input"))
      (node (ref "C4") (pin "1") (pinfunction "1_1") (pintype "unspecified"))
      (node (ref "C6") (pin "1") (pinfunction "1_1") (pintype "unspecified"))
      (node (ref "C8") (pin "1") (pinfunction "1_1") (pintype "input"))
      (node (ref "PD") (pin "11") (pinfunction "VBUS_11") (pintype "unspecified"))
      (node (ref "PD") (pin "2") (pinfunction "VBUS_2") (pintype "unspecified"))
      (node (ref "R11") (pin "2") (pinfunction "2_2") (pintype "input"))
      (node (ref "R17") (pin "2") (pinfunction "2_2") (pintype "input"))
      (node (ref "U2") (pin "11") (pinfunction "VM_11") (pintype "unspecified"))
      (node (ref "U2") (pin "4") (pinfunction "VM_4") (pintype "unspecified"))
      (node (ref "U3") (pin "7") (pinfunction "VIN_7") (pintype "unspecified"))
      (node (ref "U6") (pin "7") (pinfunction "VIN_7") (pintype "unspecified"))
    )
    (net (code "41") (name "/VUSB") (class "Default")
      (node (ref "D1") (pin "1") (pinfunction "A_1") (pintype "unspecified"))
      (node (ref "DATA") (pin "11") (pinfunction "VBUS_11") (pintype "unspecified"))
      (node (ref "DATA") (pin "2") (pinfunction "VBUS_2") (pintype "unspecified"))
      (node (ref "U7") (pin "7") (pinfunction "REGIN_7") (pintype "unspecified"))
      (node (ref "U7") (pin "8") (pinfunction "VBUS_8") (pintype "unspecified"))
    )
    (net (code "42") (name "Net-(D2-K)") (class "Default")
      (node (ref "C15") (pin "1") (pinfunction "1_1") (pintype "unspecified"))
      (node (ref "D2") (pin "1") (pinfunction "K_1") (pintype "unspecified"))
      (node (ref "L1") (pin "2") (pinfunction "2_2") (pintype "unspecified"))
      (node (ref "U6") (pin "8") (pinfunction "PH_8") (pintype "unspecified"))
    )
    (net (code "43") (name "Net-(D3-A)") (class "Default")
      (node (ref "C18") (pin "2") (pinfunction "2_2") (pintype "input"))
      (node (ref "D3") (pin "1") (pinfunction "A_1") (pintype "unspecified"))
      (node (ref "L1") (pin "1") (pinfunction "1_1") (pintype "unspecified"))
      (node (ref "R14") (pin "1") (pinfunction "1_1") (pintype "input"))
    )
    (net (code "44") (name "Net-(D6-A)") (class "Default")
      (node (ref "C7") (pin "2") (pinfunction "2_2") (pintype "input"))
      (node (ref "D6") (pin "1") (pinfunction "A_1") (pintype "unspecified"))
      (node (ref "L3") (pin "1") (pinfunction "1_1") (pintype "unspecified"))
      (node (ref "R19") (pin "1") (pinfunction "1_1") (pintype "input"))
    )
    (net (code "45") (name "Net-(D7-K)") (class "Default")
      (node (ref "C12") (pin "1") (pinfunction "1_1") (pintype "unspecified"))
      (node (ref "D7") (pin "1") (pinfunction "K_1") (pintype "unspecified"))
      (node (ref "L3") (pin "2") (pinfunction "2_2") (pintype "unspecified"))
      (node (ref "U3") (pin "8") (pinfunction "PH_8") (pintype "unspecified"))
    )
    (net (code "46") (name "Net-(DATA-CC1)") (class "Default")
      (node (ref "DATA") (pin "4") (pinfunction "CC1_4") (pintype "unspecified"))
      (node (ref "R23") (pin "2") (pinfunction "2_2") (pintype "input"))
    )
    (net (code "47") (name "Net-(DATA-CC2)") (class "Default")
      (node (ref "DATA") (pin "10") (pinfunction "CC2_10") (pintype "unspecified"))
      (node (ref "R22") (pin "2") (pinfunction "2_2") (pintype "input"))
    )
    (net (code "48") (name "Net-(PWR-K)") (class "Default")
      (node (ref "PWR") (pin "2") (pinfunction "K_2") (pintype "unspecified"))
      (node (ref "R9") (pin "2") (pinfunction "2_2") (pintype "input"))
    )
    (net (code "49") (name "Net-(Q1-B)") (class "Default")
      (node (ref "Q1") (pin "1") (pinfunction "B_1") (pintype "unspecified"))
      (node (ref "R4") (pin "1") (pinfunction "1_1") (pintype "input"))
    )
    (net (code "50") (name "Net-(Q2-B)") (class "Default")
      (node (ref "Q2") (pin "1") (pinfunction "B_1") (pintype "unspecified"))
      (node (ref "R3") (pin "2") (pinfunction "2_2") (pintype "input"))
    )
    (net (code "51") (name "Net-(R20-Pad1)") (class "Default")
      (node (ref "R20") (pin "1") (pinfunction "1_1") (pintype "input"))
      (node (ref "R21") (pin "1") (pinfunction "1_1") (pintype "unspecified"))
    )
    (net (code "52") (name "Net-(R24-Pad2)") (class "Default")
      (node (ref "R24") (pin "2") (pinfunction "2_2") (pintype "input"))
      (node (ref "R27") (pin "1") (pinfunction "1_1") (pintype "input"))
    )
    (net (code "53") (name "Net-(U2-CP1)") (class "Default")
      (node (ref "C1") (pin "2") (pinfunction "2_2") (pintype "unspecified"))
      (node (ref "U2") (pin "1") (pinfunction "CP1_1") (pintype "unspecified"))
    )
    (net (code "54") (name "Net-(U2-CP2)") (class "Default")
      (node (ref "C1") (pin "1") (pinfunction "1_1") (pintype "unspecified"))
      (node (ref "U2") (pin "2") (pinfunction "CP2_2") (pintype "unspecified"))
    )
    (net (code "55") (name "Net-(U2-V3P3OUT)") (class "Default")
      (node (ref "C5") (pin "2") (pinfunction "2_2") (pintype "unspecified"))
      (node (ref "U2") (pin "15") (pinfunction "V3P3OUT_15") (pintype "unspecified"))
    )
    (net (code "56") (name "Net-(U2-VCP)") (class "Default")
      (node (ref "C2") (pin "2") (pinfunction "2_2") (pintype "unspecified"))
      (node (ref "U2") (pin "3") (pinfunction "VCP_3") (pintype "unspecified"))
    )
    (net (code "57") (name "Net-(U3-BOOT)") (class "Default")
      (node (ref "C12") (pin "2") (pinfunction "2_2") (pintype "unspecified"))
      (node (ref "U3") (pin "1") (pinfunction "BOOT_1") (pintype "unspecified"))
    )
    (net (code "58") (name "Net-(U3-VSENSE)") (class "Default")
      (node (ref "R19") (pin "2") (pinfunction "2_2") (pintype "input"))
      (node (ref "R27") (pin "2") (pinfunction "2_2") (pintype "input"))
      (node (ref "U3") (pin "4") (pinfunction "VSENSE_4") (pintype "unspecified"))
    )
    (net (code "59") (name "Net-(U4-VBUS)") (class "Default")
      (node (ref "R17") (pin "1") (pinfunction "1_1") (pintype "input"))
      (node (ref "U4") (pin "8") (pinfunction "VBUS_8") (pintype "unspecified"))
    )
    (net (code "60") (name "Net-(U4-VDD)") (class "Default")
      (node (ref "C11") (pin "2") (pinfunction "2_2") (pintype "unspecified"))
      (node (ref "R11") (pin "1") (pinfunction "1_1") (pintype "input"))
      (node (ref "U4") (pin "1") (pinfunction "VDD_1") (pintype "unspecified"))
    )
    (net (code "61") (name "Net-(U6-BOOT)") (class "Default")
      (node (ref "C15") (pin "2") (pinfunction "2_2") (pintype "unspecified"))
      (node (ref "U6") (pin "1") (pinfunction "BOOT_1") (pintype "unspecified"))
    )
    (net (code "62") (name "Net-(U6-VSENSE)") (class "Default")
      (node (ref "R14") (pin "2") (pinfunction "2_2") (pintype "input"))
      (node (ref "R20") (pin "2") (pinfunction "2_2") (pintype "input"))
      (node (ref "U6") (pin "4") (pinfunction "VSENSE_4") (pintype "unspecified"))
    )
    (net (code "63") (name "unconnected-(DATA-SBU1-Pad9)") (class "Default")
      (node (ref "DATA") (pin "9") (pinfunction "SBU1_9") (pintype "unspecified+no_connect"))
    )
    (net (code "64") (name "unconnected-(DATA-SBU2-Pad3)") (class "Default")
      (node (ref "DATA") (pin "3") (pinfunction "SBU2_3") (pintype "unspecified+no_connect"))
    )
    (net (code "65") (name "unconnected-(PD-DN1-Pad7)") (class "Default")
      (node (ref "PD") (pin "7") (pinfunction "DN1_7") (pintype "unspecified+no_connect"))
    )
    (net (code "66") (name "unconnected-(PD-DN2-Pad5)") (class "Default")
      (node (ref "PD") (pin "5") (pinfunction "DN2_5") (pintype "unspecified+no_connect"))
    )
    (net (code "67") (name "unconnected-(PD-DP1-Pad6)") (class "Default")
      (node (ref "PD") (pin "6") (pinfunction "DP1_6") (pintype "unspecified+no_connect"))
    )
    (net (code "68") (name "unconnected-(PD-DP2-Pad8)") (class "Default")
      (node (ref "PD") (pin "8") (pinfunction "DP2_8") (pintype "unspecified+no_connect"))
    )
    (net (code "69") (name "unconnected-(PD-SBU1-Pad9)") (class "Default")
      (node (ref "PD") (pin "9") (pinfunction "SBU1_9") (pintype "unspecified+no_connect"))
    )
    (net (code "70") (name "unconnected-(PD-SBU2-Pad3)") (class "Default")
      (node (ref "PD") (pin "3") (pinfunction "SBU2_3") (pintype "unspecified+no_connect"))
    )
    (net (code "71") (name "unconnected-(SYSFAN1-Pad3)") (class "Default")
      (node (ref "SYSFAN1") (pin "3") (pinfunction "3_3") (pintype "bidirectional+no_connect"))
    )
    (net (code "72") (name "unconnected-(SYSFAN1-Pad4)") (class "Default")
      (node (ref "SYSFAN1") (pin "4") (pinfunction "4_4") (pintype "bidirectional+no_connect"))
    )
    (net (code "73") (name "unconnected-(U1-EP-Pad17)") (class "Default")
      (node (ref "U1") (pin "17") (pinfunction "EP_17") (pintype "unspecified+no_connect"))
    )
    (net (code "74") (name "unconnected-(U1-NC-Pad1)") (class "Default")
      (node (ref "U1") (pin "1") (pinfunction "NC_1") (pintype "unspecified+no_connect"))
    )
    (net (code "75") (name "unconnected-(U1-NC-Pad2)") (class "Default")
      (node (ref "U1") (pin "2") (pinfunction "NC_2") (pintype "unspecified+no_connect"))
    )
    (net (code "76") (name "unconnected-(U1-NC-Pad3)") (class "Default")
      (node (ref "U1") (pin "3") (pinfunction "NC_3") (pintype "unspecified+no_connect"))
    )
    (net (code "77") (name "unconnected-(U1-NC-Pad4)") (class "Default")
      (node (ref "U1") (pin "4") (pinfunction "NC_4") (pintype "unspecified+no_connect"))
    )
    (net (code "78") (name "unconnected-(U1-NC-Pad10)") (class "Default")
      (node (ref "U1") (pin "10") (pinfunction "NC_10") (pintype "unspecified+no_connect"))
    )
    (net (code "79") (name "unconnected-(U1-OUT-Pad15)") (class "Default")
      (node (ref "U1") (pin "15") (pinfunction "OUT_15") (pintype "unspecified+no_connect"))
    )
    (net (code "80") (name "unconnected-(U1-PUSH-Pad5)") (class "Default")
      (node (ref "U1") (pin "5") (pinfunction "PUSH_5") (pintype "unspecified+no_connect"))
    )
    (net (code "81") (name "unconnected-(U1-U-Pad11)") (class "Default")
      (node (ref "U1") (pin "11") (pinfunction "U_11") (pintype "unspecified+no_connect"))
    )
    (net (code "82") (name "unconnected-(U1-V-Pad12)") (class "Default")
      (node (ref "U1") (pin "12") (pinfunction "V_12") (pintype "unspecified+no_connect"))
    )
    (net (code "83") (name "unconnected-(U1-W-Pad9)") (class "Default")
      (node (ref "U1") (pin "9") (pinfunction "W_9") (pintype "unspecified+no_connect"))
    )
    (net (code "84") (name "unconnected-(U2-COMPO#-Pad19)") (class "Default")
      (node (ref "U2") (pin "19") (pinfunction "COMPO#_19") (pintype "unspecified+no_connect"))
    )
    (net (code "85") (name "unconnected-(U2-NC-Pad21)") (class "Default")
      (node (ref "U2") (pin "21") (pinfunction "NC_21") (pintype "unspecified+no_connect"))
    )
    (net (code "86") (name "unconnected-(U3-ENA-Pad5)") (class "Default")
      (node (ref "U3") (pin "5") (pinfunction "ENA_5") (pintype "unspecified+no_connect"))
    )
    (net (code "87") (name "unconnected-(U3-NC-Pad2)") (class "Default")
      (node (ref "U3") (pin "2") (pinfunction "NC_2") (pintype "unspecified+no_connect"))
    )
    (net (code "88") (name "unconnected-(U3-NC-Pad3)") (class "Default")
      (node (ref "U3") (pin "3") (pinfunction "NC_3") (pintype "unspecified+no_connect"))
    )
    (net (code "89") (name "unconnected-(U4-CFG1-Pad9)") (class "Default")
      (node (ref "U4") (pin "9") (pinfunction "CFG1_9") (pintype "unspecified+no_connect"))
    )
    (net (code "90") (name "unconnected-(U4-CFG2-Pad2)") (class "Default")
      (node (ref "U4") (pin "2") (pinfunction "CFG2_2") (pintype "unspecified+no_connect"))
    )
    (net (code "91") (name "unconnected-(U4-CFG3-Pad3)") (class "Default")
      (node (ref "U4") (pin "3") (pinfunction "CFG3_3") (pintype "unspecified+no_connect"))
    )
    (net (code "92") (name "unconnected-(U4-DM-Pad5)") (class "Default")
      (node (ref "U4") (pin "5") (pinfunction "DM_5") (pintype "unspecified+no_connect"))
    )
    (net (code "93") (name "unconnected-(U4-DP-Pad4)") (class "Default")
      (node (ref "U4") (pin "4") (pinfunction "DP_4") (pintype "unspecified+no_connect"))
    )
    (net (code "94") (name "unconnected-(U4-PG-Pad10)") (class "Default")
      (node (ref "U4") (pin "10") (pinfunction "PG_10") (pintype "unspecified+no_connect"))
    )
    (net (code "95") (name "unconnected-(U5-IO23-Pad37)") (class "Default")
      (node (ref "U5") (pin "37") (pinfunction "IO23_37") (pintype "unspecified+no_connect"))
    )
    (net (code "96") (name "unconnected-(U5-IO32-Pad8)") (class "Default")
      (node (ref "U5") (pin "8") (pinfunction "IO32_8") (pintype "unspecified+no_connect"))
    )
    (net (code "97") (name "unconnected-(U5-IO34-Pad6)") (class "Default")
      (node (ref "U5") (pin "6") (pinfunction "IO34_6") (pintype "unspecified+no_connect"))
    )
    (net (code "98") (name "unconnected-(U5-IO35-Pad7)") (class "Default")
      (node (ref "U5") (pin "7") (pinfunction "IO35_7") (pintype "unspecified+no_connect"))
    )
    (net (code "99") (name "unconnected-(U5-NC-Pad17)") (class "Default")
      (node (ref "U5") (pin "17") (pinfunction "NC_17") (pintype "unspecified+no_connect"))
    )
    (net (code "100") (name "unconnected-(U5-NC-Pad18)") (class "Default")
      (node (ref "U5") (pin "18") (pinfunction "NC_18") (pintype "unspecified+no_connect"))
    )
    (net (code "101") (name "unconnected-(U5-NC-Pad19)") (class "Default")
      (node (ref "U5") (pin "19") (pinfunction "NC_19") (pintype "unspecified+no_connect"))
    )
    (net (code "102") (name "unconnected-(U5-NC-Pad20)") (class "Default")
      (node (ref "U5") (pin "20") (pinfunction "NC_20") (pintype "unspecified+no_connect"))
    )
    (net (code "103") (name "unconnected-(U5-NC-Pad21)") (class "Default")
      (node (ref "U5") (pin "21") (pinfunction "NC_21") (pintype "unspecified+no_connect"))
    )
    (net (code "104") (name "unconnected-(U5-NC-Pad22)") (class "Default")
      (node (ref "U5") (pin "22") (pinfunction "NC_22") (pintype "unspecified+no_connect"))
    )
    (net (code "105") (name "unconnected-(U5-NC-Pad32)") (class "Default")
      (node (ref "U5") (pin "32") (pinfunction "NC_32") (pintype "unspecified+no_connect"))
    )
    (net (code "106") (name "unconnected-(U5-SENSOR_VN-Pad5)") (class "Default")
      (node (ref "U5") (pin "5") (pinfunction "SENSOR_VN_5") (pintype "unspecified+no_connect"))
    )
    (net (code "107") (name "unconnected-(U5-SENSOR_VP-Pad4)") (class "Default")
      (node (ref "U5") (pin "4") (pinfunction "SENSOR_VP_4") (pintype "unspecified+no_connect"))
    )
    (net (code "108") (name "unconnected-(U6-ENA-Pad5)") (class "Default")
      (node (ref "U6") (pin "5") (pinfunction "ENA_5") (pintype "unspecified+no_connect"))
    )
    (net (code "109") (name "unconnected-(U6-NC-Pad2)") (class "Default")
      (node (ref "U6") (pin "2") (pinfunction "NC_2") (pintype "unspecified+no_connect"))
    )
    (net (code "110") (name "unconnected-(U6-NC-Pad3)") (class "Default")
      (node (ref "U6") (pin "3") (pinfunction "NC_3") (pintype "unspecified+no_connect"))
    )
    (net (code "111") (name "unconnected-(U7-CTS-Pad23)") (class "Default")
      (node (ref "U7") (pin "23") (pinfunction "CTS_23") (pintype "unspecified+no_connect"))
    )
    (net (code "112") (name "unconnected-(U7-DCD-Pad1)") (class "Default")
      (node (ref "U7") (pin "1") (pinfunction "DCD_1") (pintype "unspecified+no_connect"))
    )
    (net (code "113") (name "unconnected-(U7-DSR-Pad27)") (class "Default")
      (node (ref "U7") (pin "27") (pinfunction "DSR_27") (pintype "unspecified+no_connect"))
    )
    (net (code "114") (name "unconnected-(U7-NC-Pad10)") (class "Default")
      (node (ref "U7") (pin "10") (pinfunction "NC_10") (pintype "unspecified+no_connect"))
    )
    (net (code "115") (name "unconnected-(U7-NC-Pad13)") (class "Default")
      (node (ref "U7") (pin "13") (pinfunction "NC_13") (pintype "unspecified+no_connect"))
    )
    (net (code "116") (name "unconnected-(U7-NC-Pad14)") (class "Default")
      (node (ref "U7") (pin "14") (pinfunction "NC_14") (pintype "unspecified+no_connect"))
    )
    (net (code "117") (name "unconnected-(U7-NC-Pad15)") (class "Default")
      (node (ref "U7") (pin "15") (pinfunction "NC_15") (pintype "unspecified+no_connect"))
    )
    (net (code "118") (name "unconnected-(U7-NC-Pad16)") (class "Default")
      (node (ref "U7") (pin "16") (pinfunction "NC_16") (pintype "unspecified+no_connect"))
    )
    (net (code "119") (name "unconnected-(U7-NC-Pad17)") (class "Default")
      (node (ref "U7") (pin "17") (pinfunction "NC_17") (pintype "unspecified+no_connect"))
    )
    (net (code "120") (name "unconnected-(U7-NC-Pad18)") (class "Default")
      (node (ref "U7") (pin "18") (pinfunction "NC_18") (pintype "unspecified+no_connect"))
    )
    (net (code "121") (name "unconnected-(U7-NC-Pad19)") (class "Default")
      (node (ref "U7") (pin "19") (pinfunction "NC_19") (pintype "unspecified+no_connect"))
    )
    (net (code "122") (name "unconnected-(U7-NC-Pad20)") (class "Default")
      (node (ref "U7") (pin "20") (pinfunction "NC_20") (pintype "unspecified+no_connect"))
    )
    (net (code "123") (name "unconnected-(U7-NC-Pad21)") (class "Default")
      (node (ref "U7") (pin "21") (pinfunction "NC_21") (pintype "unspecified+no_connect"))
    )
    (net (code "124") (name "unconnected-(U7-NC-Pad22)") (class "Default")
      (node (ref "U7") (pin "22") (pinfunction "NC_22") (pintype "unspecified+no_connect"))
    )
    (net (code "125") (name "unconnected-(U7-RI-Pad2)") (class "Default")
      (node (ref "U7") (pin "2") (pinfunction "RI_2") (pintype "unspecified+no_connect"))
    )
    (net (code "126") (name "unconnected-(U7-SUSPEND#-Pad11)") (class "Default")
      (node (ref "U7") (pin "11") (pinfunction "SUSPEND#_11") (pintype "unspecified+no_connect"))
    )
    (net (code "127") (name "unconnected-(U7-SUSPEND-Pad12)") (class "Default")
      (node (ref "U7") (pin "12") (pinfunction "SUSPEND_12") (pintype "unspecified+no_connect"))
    )
  )
)
